# DMC_Tracer.net
KiCad netlist of a schematic drawn in EAGLE
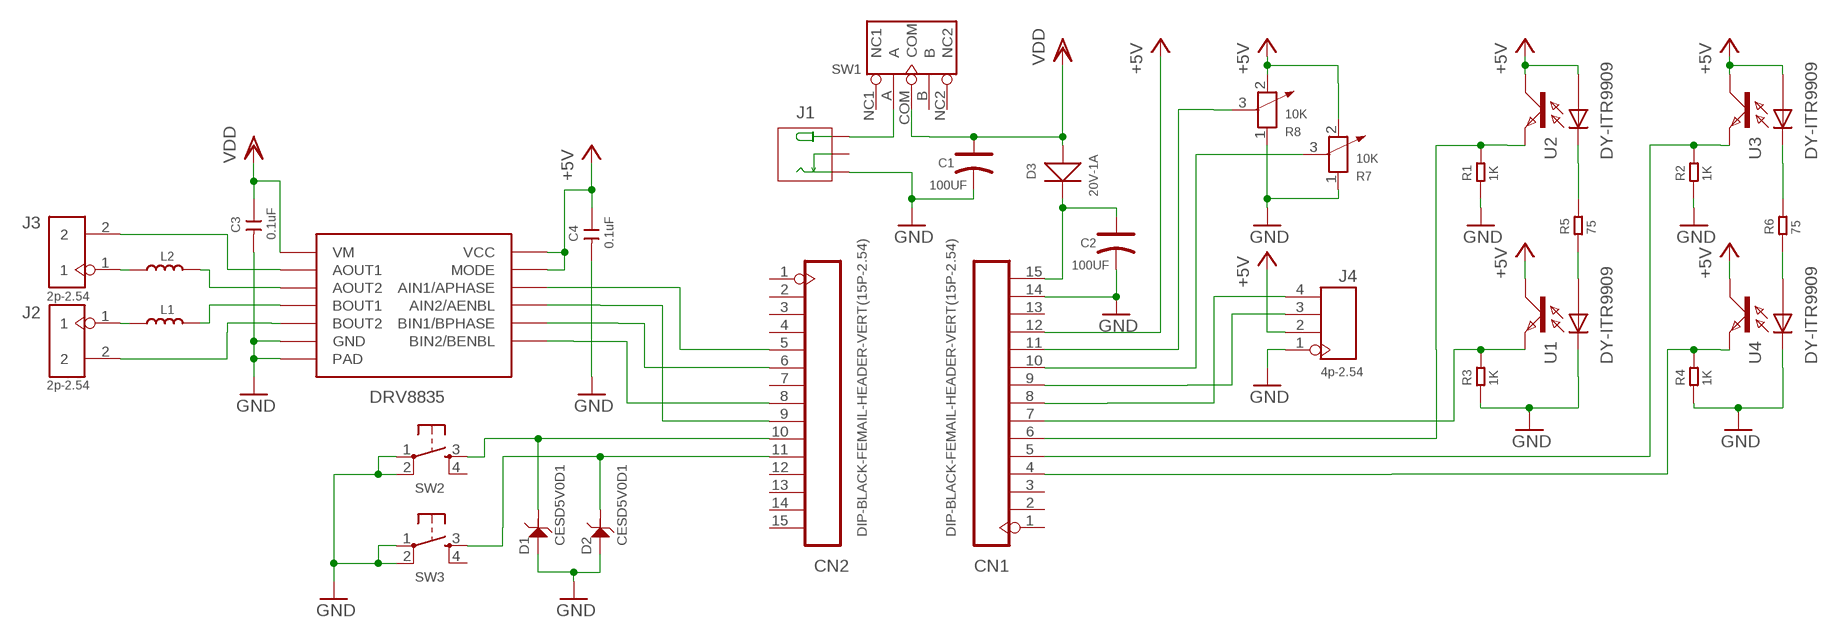
[diagram p0: schematic, sheet 1]

(export (version "E")
  (design (tool "Eeschema 10.0.6"))
  (components
    (comp (ref "C1")
      (value "100UF")
      (footprint "eagle-import:ELECTRO-SMD-C-6MM")
      (fields (field (name "MPN") "CS1E470M-CRE54"))
      (libsource (lib "eagle-import") (part "ALUMINUM-SMD-47UF-25V(D6.3-H5.3MM)"))
    )
    (comp (ref "C2")
      (value "100UF")
      (footprint "eagle-import:ELECTRO-SMD-C-6MM")
      (fields (field (name "MPN") "CS1E470M-CRE54"))
      (libsource (lib "eagle-import") (part "ALUMINUM-SMD-47UF-25V(D6.3-H5.3MM)"))
    )
    (comp (ref "C3")
      (value "0.1uF")
      (footprint "eagle-import:C0603")
      (fields (field (name "MPN") "CC0603KRX7R9BB104"))
      (libsource (lib "eagle-import") (part "CERAMIC-100NF-50V-10%-X7R(0603)"))
    )
    (comp (ref "C4")
      (value "0.1uF")
      (footprint "eagle-import:C0603")
      (fields (field (name "MPN") "CC0603KRX7R9BB104"))
      (libsource (lib "eagle-import") (part "CERAMIC-100NF-50V-10%-X7R(0603)"))
    )
    (comp (ref "CN1")
      (value "DIP-BLACK-FEMAIL-HEADER-VERT(15P-2.54)")
      (footprint "eagle-import:H15-2.54")
      (libsource (lib "eagle-import") (part "DIP-BLACK-FEMAIL-HEADER-VERT(15P-2.54)"))
    )
    (comp (ref "CN2")
      (value "DIP-BLACK-FEMAIL-HEADER-VERT(15P-2.54)")
      (footprint "eagle-import:H15-2.54")
      (libsource (lib "eagle-import") (part "DIP-BLACK-FEMAIL-HEADER-VERT(15P-2.54)"))
    )
    (comp (ref "D1")
      (value "CESD5V0D1")
      (footprint "eagle-import:SOD-123")
      (libsource (lib "eagle-import") (part "SMD-DIODE-ESD-6.2V-250MW(SOD-123)"))
    )
    (comp (ref "D2")
      (value "CESD5V0D1")
      (footprint "eagle-import:SOD-123")
      (libsource (lib "eagle-import") (part "SMD-DIODE-ESD-6.2V-250MW(SOD-123)"))
    )
    (comp (ref "D3")
      (value "20V-1A")
      (footprint "eagle-import:SOD-123")
      (fields (field (name "MPN") "B5819W"))
      (libsource (lib "eagle-import") (part "SMD-DIODE-SCHOTTKY-20V-1A(SOD-123)"))
    )
    (comp (ref "J1")
      (value "DC-005")
      (footprint "eagle-import:3P-L14.2_W11.0_H9.0MM")
      (libsource (lib "eagle-import") (part "JACK-DC-005'DC-005'"))
    )
    (comp (ref "J2")
      (value "2p-2.54")
      (footprint "eagle-import:H2-2.54")
      (fields (field (name "MPN") "P125-1102A0BS116A1"))
      (libsource (lib "eagle-import") (part "DIP-BLACK-MALE-HEADER-VERT(2P-2.54)"))
    )
    (comp (ref "J3")
      (value "2p-2.54")
      (footprint "eagle-import:H2-2.54")
      (fields (field (name "MPN") "P125-1102A0BS116A1"))
      (libsource (lib "eagle-import") (part "DIP-BLACK-MALE-HEADER-VERT(2P-2.54)"))
    )
    (comp (ref "J4")
      (value "4p-2.54")
      (footprint "eagle-import:H4-2.54")
      (fields (field (name "MPN") "F185-1104A1BSYA1"))
      (libsource (lib "eagle-import") (part "DIP-BLACK-FEMALE-HEADER-VERT(4P-2.54)"))
    )
    (comp (ref "L1")
      (value "SMD-INDUCTOR(2P-8X8MM)")
      (footprint "eagle-import:L8040")
      (libsource (lib "eagle-import") (part "SMD-INDUCTOR(2P-8X8MM)"))
    )
    (comp (ref "L2")
      (value "SMD-INDUCTOR(2P-8X8MM)")
      (footprint "eagle-import:L8040")
      (libsource (lib "eagle-import") (part "SMD-INDUCTOR(2P-8X8MM)"))
    )
    (comp (ref "R1")
      (value "1K")
      (footprint "eagle-import:R0805")
      (fields (field (name "MPN") "RC0805JR-071KL"))
      (libsource (lib "eagle-import") (part "SMD-RES-1K-5%-1/8W(0805)"))
    )
    (comp (ref "R2")
      (value "1K")
      (footprint "eagle-import:R0805")
      (fields (field (name "MPN") "RC0805JR-071KL"))
      (libsource (lib "eagle-import") (part "SMD-RES-1K-5%-1/8W(0805)"))
    )
    (comp (ref "R3")
      (value "1K")
      (footprint "eagle-import:R0805")
      (fields (field (name "MPN") "RC0805JR-071KL"))
      (libsource (lib "eagle-import") (part "SMD-RES-1K-5%-1/8W(0805)"))
    )
    (comp (ref "R4")
      (value "1K")
      (footprint "eagle-import:R0805")
      (fields (field (name "MPN") "RC0805JR-071KL"))
      (libsource (lib "eagle-import") (part "SMD-RES-1K-5%-1/8W(0805)"))
    )
    (comp (ref "R5")
      (value "75")
      (footprint "eagle-import:R0805")
      (fields (field (name "MPN") "RC0805JR-071KL"))
      (libsource (lib "eagle-import") (part "SMD-RES-75R-1%-1/8W(0805)"))
    )
    (comp (ref "R6")
      (value "75")
      (footprint "eagle-import:R0805")
      (fields (field (name "MPN") "RC0805JR-071KL"))
      (libsource (lib "eagle-import") (part "SMD-RES-75R-1%-1/8W(0805)"))
    )
    (comp (ref "R7")
      (value "10K")
      (footprint "eagle-import:ADJR3-7.0X7.0X5.0MM")
      (fields (field (name "MPN") "SX3362P"))
      (libsource (lib "eagle-import") (part "DIP-VR-TOP-ADJ-1K-3362P(3P-7.0X7.0X5.0MM)"))
    )
    (comp (ref "R8")
      (value "10K")
      (footprint "eagle-import:ADJR3-7.0X7.0X5.0MM")
      (fields (field (name "MPN") "SX3362P"))
      (libsource (lib "eagle-import") (part "DIP-VR-TOP-ADJ-1K-3362P(3P-7.0X7.0X5.0MM)"))
    )
    (comp (ref "SW1")
      (value "DIP-TOGGLE-SWITCH-ON-ON(3+2P-8.8X4.6MM)-90D")
      (footprint "eagle-import:SW5-2.0-8.8X4.4X4.7MM-90D")
      (fields (field (name "MPN") "3P-2.0-90D3P-2.0-90D-REINFORCE"))
      (libsource (lib "eagle-import") (part "DIP-TOGGLE-SWITCH-ON-ON(3+2P-8.8X4.6MM)-90D"))
    )
    (comp (ref "SW2")
      (value "T-SWITCH-10-SEEED")
      (footprint "eagle-import:B3F-10XX-SEEED")
      (libsource (lib "eagle-import") (part "T-SWITCH-10-SEEED"))
    )
    (comp (ref "SW3")
      (value "T-SWITCH-10-SEEED")
      (footprint "eagle-import:B3F-10XX-SEEED")
      (libsource (lib "eagle-import") (part "T-SWITCH-10-SEEED"))
    )
    (comp (ref "U$1")
      (value "DRV8835")
      (footprint "eagle-import:WSON12")
      (libsource (lib "eagle-import") (part "DRV8835"))
    )
    (comp (ref "U1")
      (value "DY-ITR9909")
      (footprint "eagle-import:DY-ITR9909")
      (libsource (lib "eagle-import") (part "DY-ITR9909"))
    )
    (comp (ref "U2")
      (value "DY-ITR9909")
      (footprint "eagle-import:DY-ITR9909")
      (libsource (lib "eagle-import") (part "DY-ITR9909"))
    )
    (comp (ref "U3")
      (value "DY-ITR9909")
      (footprint "eagle-import:DY-ITR9909")
      (libsource (lib "eagle-import") (part "DY-ITR9909"))
    )
    (comp (ref "U4")
      (value "DY-ITR9909")
      (footprint "eagle-import:DY-ITR9909")
      (libsource (lib "eagle-import") (part "DY-ITR9909"))
    )
  )
  (nets
    (net (code "1") (name "+5V") (class "Default")
      (node (ref "C4") (pin "1") (pinfunction "1_1") (pintype "passive"))
      (node (ref "CN1") (pin "12") (pinfunction "12_12") (pintype "passive"))
      (node (ref "J4") (pin "2") (pinfunction "P$2_2") (pintype "bidirectional"))
      (node (ref "R7") (pin "2") (pinfunction "2_2") (pintype "passive"))
      (node (ref "R8") (pin "2") (pinfunction "2_2") (pintype "passive"))
      (node (ref "U$1") (pin "P$11") (pinfunction "MODE_P$11") (pintype "input"))
      (node (ref "U$1") (pin "P$12") (pinfunction "VCC_P$12") (pintype "power_in"))
      (node (ref "U1") (pin "C") (pinfunction "C_C") (pintype "passive"))
      (node (ref "U2") (pin "A") (pinfunction "A_A") (pintype "passive"))
      (node (ref "U2") (pin "C") (pinfunction "C_C") (pintype "passive"))
      (node (ref "U3") (pin "A") (pinfunction "A_A") (pintype "passive"))
      (node (ref "U3") (pin "C") (pinfunction "C_C") (pintype "passive"))
      (node (ref "U4") (pin "C") (pinfunction "C_C") (pintype "passive"))
    )
    (net (code "2") (name "GND") (class "Default")
      (node (ref "C1") (pin "-") (pinfunction "-_-") (pintype "passive"))
      (node (ref "C2") (pin "-") (pinfunction "-_-") (pintype "passive"))
      (node (ref "C3") (pin "2") (pinfunction "2_2") (pintype "passive"))
      (node (ref "C4") (pin "2") (pinfunction "2_2") (pintype "passive"))
      (node (ref "CN1") (pin "14") (pinfunction "14_14") (pintype "passive"))
      (node (ref "D1") (pin "+") (pinfunction "1_+") (pintype "bidirectional"))
      (node (ref "D2") (pin "+") (pinfunction "1_+") (pintype "bidirectional"))
      (node (ref "J1") (pin "-1") (pinfunction "-_-1") (pintype "bidirectional"))
      (node (ref "J4") (pin "1") (pinfunction "P$1_1") (pintype "bidirectional"))
      (node (ref "R1") (pin "1") (pinfunction "1_1") (pintype "passive"))
      (node (ref "R2") (pin "1") (pinfunction "1_1") (pintype "passive"))
      (node (ref "R3") (pin "1") (pinfunction "1_1") (pintype "passive"))
      (node (ref "R4") (pin "1") (pinfunction "1_1") (pintype "passive"))
      (node (ref "R7") (pin "1") (pinfunction "1_1") (pintype "passive"))
      (node (ref "R8") (pin "1") (pinfunction "1_1") (pintype "passive"))
      (node (ref "SW2") (pin "1") (pinfunction "P_1") (pintype "passive"))
      (node (ref "SW2") (pin "2") (pinfunction "P1_2") (pintype "passive"))
      (node (ref "SW3") (pin "1") (pinfunction "P_1") (pintype "passive"))
      (node (ref "SW3") (pin "2") (pinfunction "P1_2") (pintype "passive"))
      (node (ref "U$1") (pin "P$13") (pinfunction "PAD_P$13") (pintype "power_in"))
      (node (ref "U$1") (pin "P$14") (pinfunction "GND_P$14") (pintype "power_in"))
      (node (ref "U$1") (pin "P$6") (pinfunction "GND_P$6") (pintype "power_in"))
      (node (ref "U1") (pin "K") (pinfunction "K_K") (pintype "passive"))
      (node (ref "U4") (pin "K") (pinfunction "K_K") (pintype "passive"))
    )
    (net (code "3") (name "Net-(C2-Pad+)") (class "Default")
      (node (ref "C2") (pin "+") (pinfunction "+_+") (pintype "passive"))
      (node (ref "CN1") (pin "15") (pinfunction "15_15") (pintype "passive"))
      (node (ref "D3") (pin "-") (pinfunction "-_-") (pintype "passive"))
    )
    (net (code "4") (name "Net-(CN1-Pad4)") (class "Default")
      (node (ref "CN1") (pin "4") (pinfunction "4_4") (pintype "passive"))
      (node (ref "R4") (pin "2") (pinfunction "2_2") (pintype "passive"))
      (node (ref "U4") (pin "E") (pinfunction "E_E") (pintype "passive"))
    )
    (net (code "5") (name "Net-(CN1-Pad5)") (class "Default")
      (node (ref "CN1") (pin "5") (pinfunction "5_5") (pintype "passive"))
      (node (ref "R2") (pin "2") (pinfunction "2_2") (pintype "passive"))
      (node (ref "U3") (pin "E") (pinfunction "E_E") (pintype "passive"))
    )
    (net (code "6") (name "Net-(CN1-Pad6)") (class "Default")
      (node (ref "CN1") (pin "6") (pinfunction "6_6") (pintype "passive"))
      (node (ref "R1") (pin "2") (pinfunction "2_2") (pintype "passive"))
      (node (ref "U2") (pin "E") (pinfunction "E_E") (pintype "passive"))
    )
    (net (code "7") (name "Net-(CN1-Pad7)") (class "Default")
      (node (ref "CN1") (pin "7") (pinfunction "7_7") (pintype "passive"))
      (node (ref "R3") (pin "2") (pinfunction "2_2") (pintype "passive"))
      (node (ref "U1") (pin "E") (pinfunction "E_E") (pintype "passive"))
    )
    (net (code "8") (name "Net-(CN1-Pad10)") (class "Default")
      (node (ref "CN1") (pin "10") (pinfunction "10_10") (pintype "passive"))
      (node (ref "R7") (pin "3") (pinfunction "3_3") (pintype "passive"))
    )
    (net (code "9") (name "Net-(CN1-Pad11)") (class "Default")
      (node (ref "CN1") (pin "11") (pinfunction "11_11") (pintype "passive"))
      (node (ref "R8") (pin "3") (pinfunction "3_3") (pintype "passive"))
    )
    (net (code "10") (name "Net-(D1-2)") (class "Default")
      (node (ref "CN2") (pin "10") (pinfunction "10_10") (pintype "passive"))
      (node (ref "D1") (pin "-") (pinfunction "2_-") (pintype "bidirectional"))
      (node (ref "SW2") (pin "3") (pinfunction "S_3") (pintype "passive"))
    )
    (net (code "11") (name "Net-(D2-2)") (class "Default")
      (node (ref "CN2") (pin "11") (pinfunction "11_11") (pintype "passive"))
      (node (ref "D2") (pin "-") (pinfunction "2_-") (pintype "bidirectional"))
      (node (ref "SW3") (pin "3") (pinfunction "S_3") (pintype "passive"))
    )
    (net (code "12") (name "Net-(J1-Pad+)") (class "Default")
      (node (ref "J1") (pin "+") (pinfunction "+_+") (pintype "bidirectional"))
      (node (ref "SW1") (pin "A") (pinfunction "A_A") (pintype "bidirectional"))
    )
    (net (code "13") (name "Net-(J2-Pad1)") (class "Default")
      (node (ref "J2") (pin "1") (pinfunction "1_1") (pintype "bidirectional"))
      (node (ref "L1") (pin "1") (pinfunction "1_1") (pintype "passive"))
    )
    (net (code "14") (name "Net-(J3-Pad1)") (class "Default")
      (node (ref "J3") (pin "1") (pinfunction "1_1") (pintype "bidirectional"))
      (node (ref "L2") (pin "1") (pinfunction "1_1") (pintype "passive"))
    )
    (net (code "15") (name "Net-(J4-P$3)") (class "Default")
      (node (ref "CN1") (pin "9") (pinfunction "9_9") (pintype "passive"))
      (node (ref "J4") (pin "3") (pinfunction "P$3_3") (pintype "bidirectional"))
    )
    (net (code "16") (name "Net-(J4-P$4)") (class "Default")
      (node (ref "CN1") (pin "8") (pinfunction "8_8") (pintype "passive"))
      (node (ref "J4") (pin "4") (pinfunction "P$4_4") (pintype "bidirectional"))
    )
    (net (code "17") (name "Net-(R5-Pad1)") (class "Default")
      (node (ref "R5") (pin "1") (pinfunction "1_1") (pintype "passive"))
      (node (ref "U1") (pin "A") (pinfunction "A_A") (pintype "passive"))
    )
    (net (code "18") (name "Net-(R5-Pad2)") (class "Default")
      (node (ref "R5") (pin "2") (pinfunction "2_2") (pintype "passive"))
      (node (ref "U2") (pin "K") (pinfunction "K_K") (pintype "passive"))
    )
    (net (code "19") (name "Net-(R6-Pad1)") (class "Default")
      (node (ref "R6") (pin "1") (pinfunction "1_1") (pintype "passive"))
      (node (ref "U4") (pin "A") (pinfunction "A_A") (pintype "passive"))
    )
    (net (code "20") (name "Net-(R6-Pad2)") (class "Default")
      (node (ref "R6") (pin "2") (pinfunction "2_2") (pintype "passive"))
      (node (ref "U3") (pin "K") (pinfunction "K_K") (pintype "passive"))
    )
    (net (code "21") (name "Net-(U$1-AIN1{slash}APHASE)") (class "Default")
      (node (ref "CN2") (pin "5") (pinfunction "5_5") (pintype "passive"))
      (node (ref "U$1") (pin "P$10") (pinfunction "AIN1/APHASE_P$10") (pintype "input"))
    )
    (net (code "22") (name "Net-(U$1-AIN2{slash}AENBL)") (class "Default")
      (node (ref "CN2") (pin "9") (pinfunction "9_9") (pintype "passive"))
      (node (ref "U$1") (pin "P$9") (pinfunction "AIN2/AENBL_P$9") (pintype "input"))
    )
    (net (code "23") (name "Net-(U$1-AOUT1)") (class "Default")
      (node (ref "J3") (pin "2") (pinfunction "2_2") (pintype "bidirectional"))
      (node (ref "U$1") (pin "P$2") (pinfunction "AOUT1_P$2") (pintype "output"))
    )
    (net (code "24") (name "Net-(U$1-AOUT2)") (class "Default")
      (node (ref "L2") (pin "2") (pinfunction "2_2") (pintype "passive"))
      (node (ref "U$1") (pin "P$3") (pinfunction "AOUT2_P$3") (pintype "output"))
    )
    (net (code "25") (name "Net-(U$1-BIN1{slash}BPHASE)") (class "Default")
      (node (ref "CN2") (pin "6") (pinfunction "6_6") (pintype "passive"))
      (node (ref "U$1") (pin "P$8") (pinfunction "BIN1/BPHASE_P$8") (pintype "input"))
    )
    (net (code "26") (name "Net-(U$1-BIN2{slash}BENBL)") (class "Default")
      (node (ref "CN2") (pin "8") (pinfunction "8_8") (pintype "passive"))
      (node (ref "U$1") (pin "P$7") (pinfunction "BIN2/BENBL_P$7") (pintype "input"))
    )
    (net (code "27") (name "Net-(U$1-BOUT1)") (class "Default")
      (node (ref "L1") (pin "2") (pinfunction "2_2") (pintype "passive"))
      (node (ref "U$1") (pin "P$4") (pinfunction "BOUT1_P$4") (pintype "output"))
    )
    (net (code "28") (name "Net-(U$1-BOUT2)") (class "Default")
      (node (ref "J2") (pin "2") (pinfunction "2_2") (pintype "bidirectional"))
      (node (ref "U$1") (pin "P$5") (pinfunction "BOUT2_P$5") (pintype "output"))
    )
    (net (code "29") (name "VDD") (class "Default")
      (node (ref "C1") (pin "+") (pinfunction "+_+") (pintype "passive"))
      (node (ref "C3") (pin "1") (pinfunction "1_1") (pintype "passive"))
      (node (ref "D3") (pin "+") (pinfunction "+_+") (pintype "passive"))
      (node (ref "SW1") (pin "COM") (pinfunction "COM_COM") (pintype "bidirectional"))
      (node (ref "U$1") (pin "P$1") (pinfunction "VM_P$1") (pintype "power_in"))
    )
    (net (code "30") (name "unconnected-(CN1-Pad1)") (class "Default")
      (node (ref "CN1") (pin "1") (pinfunction "1_1") (pintype "passive"))
    )
    (net (code "31") (name "unconnected-(CN1-Pad2)") (class "Default")
      (node (ref "CN1") (pin "2") (pinfunction "2_2") (pintype "passive"))
    )
    (net (code "32") (name "unconnected-(CN1-Pad3)") (class "Default")
      (node (ref "CN1") (pin "3") (pinfunction "3_3") (pintype "passive"))
    )
    (net (code "33") (name "unconnected-(CN1-Pad13)") (class "Default")
      (node (ref "CN1") (pin "13") (pinfunction "13_13") (pintype "passive"))
    )
    (net (code "34") (name "unconnected-(CN2-Pad1)") (class "Default")
      (node (ref "CN2") (pin "1") (pinfunction "1_1") (pintype "passive"))
    )
    (net (code "35") (name "unconnected-(CN2-Pad2)") (class "Default")
      (node (ref "CN2") (pin "2") (pinfunction "2_2") (pintype "passive"))
    )
    (net (code "36") (name "unconnected-(CN2-Pad3)") (class "Default")
      (node (ref "CN2") (pin "3") (pinfunction "3_3") (pintype "passive"))
    )
    (net (code "37") (name "unconnected-(CN2-Pad4)") (class "Default")
      (node (ref "CN2") (pin "4") (pinfunction "4_4") (pintype "passive"))
    )
    (net (code "38") (name "unconnected-(CN2-Pad7)") (class "Default")
      (node (ref "CN2") (pin "7") (pinfunction "7_7") (pintype "passive"))
    )
    (net (code "39") (name "unconnected-(CN2-Pad12)") (class "Default")
      (node (ref "CN2") (pin "12") (pinfunction "12_12") (pintype "passive"))
    )
    (net (code "40") (name "unconnected-(CN2-Pad13)") (class "Default")
      (node (ref "CN2") (pin "13") (pinfunction "13_13") (pintype "passive"))
    )
    (net (code "41") (name "unconnected-(CN2-Pad14)") (class "Default")
      (node (ref "CN2") (pin "14") (pinfunction "14_14") (pintype "passive"))
    )
    (net (code "42") (name "unconnected-(CN2-Pad15)") (class "Default")
      (node (ref "CN2") (pin "15") (pinfunction "15_15") (pintype "passive"))
    )
    (net (code "43") (name "unconnected-(J1-CDN-Pad-2)") (class "Default")
      (node (ref "J1") (pin "-2") (pinfunction "CDN_-2") (pintype "bidirectional"))
    )
    (net (code "44") (name "unconnected-(SW1-PadB)") (class "Default")
      (node (ref "SW1") (pin "B") (pinfunction "B_B") (pintype "bidirectional"))
    )
    (net (code "45") (name "unconnected-(SW1-PadNC1)") (class "Default")
      (node (ref "SW1") (pin "NC1") (pinfunction "NC1_NC1") (pintype "bidirectional"))
    )
    (net (code "46") (name "unconnected-(SW1-PadNC2)") (class "Default")
      (node (ref "SW1") (pin "NC2") (pinfunction "NC2_NC2") (pintype "bidirectional"))
    )
    (net (code "47") (name "unconnected-(SW2-S1-Pad4)") (class "Default")
      (node (ref "SW2") (pin "4") (pinfunction "S1_4") (pintype "passive"))
    )
    (net (code "48") (name "unconnected-(SW3-S1-Pad4)") (class "Default")
      (node (ref "SW3") (pin "4") (pinfunction "S1_4") (pintype "passive"))
    )
  )
)
